# 6_3-axis-accelerometer.net
KiCad netlist of a schematic drawn in Altium Designer
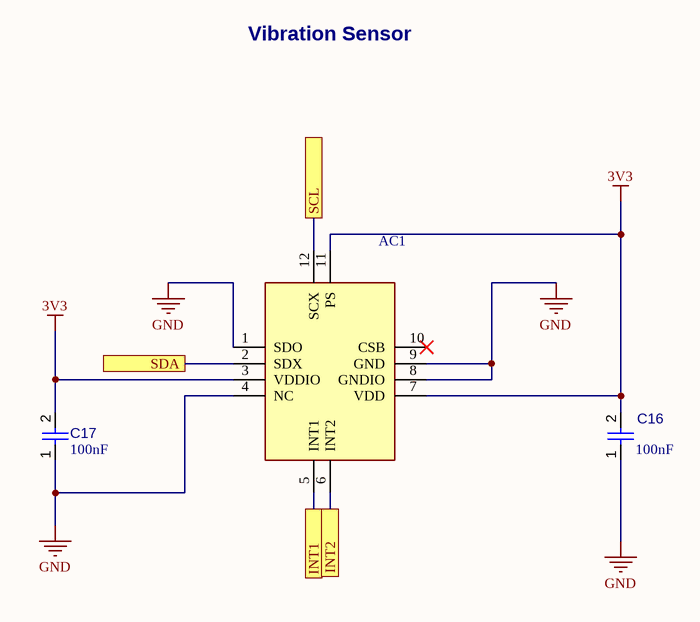
[diagram p0: [6]3-axis-accelerometer.SchDoc]

(export (version "E")
  (design (tool "Eeschema 10.0.6"))
  (components
    (comp (ref "AC1")
      (value "BMA490L")
      (footprint "BMA280")
      (description "BMA490L Accelerometer")
      (fields
        (field (name "MANUFACTURER_PART_NUMBER") "BMA280")
        (field (name "MOUSER PART NUMBER") "262-BMA280")
      )
      (libsource (lib "PCB_High_Voltage_Sensor") (part "BMA280"))
    )
    (comp (ref "C16")
      (value "100nF")
      (footprint "CAPC1608X90X40ML10T20")
      (description "Chip Capacitor, 100 nF, +/- 10%, 50 V, 0603 (1608 Metric)")
      (fields (field (name "TOLERANCE") "10%") (field (name "Comment") "Capacitor 100 nF +/-10% 50 V 0603"))
      (libsource (lib "Latium Technologies") (part "CAP-NP-2"))
    )
    (comp (ref "C17")
      (value "100nF")
      (footprint "CAPC1608X90X40ML10T20")
      (description "Chip Capacitor, 100 nF, +/- 10%, 50 V, 0603 (1608 Metric)")
      (fields (field (name "TOLERANCE") "10%") (field (name "Comment") "Capacitor 100 nF +/-10% 50 V 0603"))
      (libsource (lib "Latium Technologies") (part "CAP-NP-2"))
    )
  )
  (nets
    (net (code "1") (name "/INT1") (class "Default")
      (node (ref "AC1") (pin "5") (pinfunction "INT1_5") (pintype "passive"))
    )
    (net (code "2") (name "/INT2") (class "Default")
      (node (ref "AC1") (pin "6") (pinfunction "INT2_6") (pintype "passive"))
    )
    (net (code "3") (name "/SCL") (class "Default")
      (node (ref "AC1") (pin "12") (pinfunction "SCX_12") (pintype "passive"))
    )
    (net (code "4") (name "/SDA") (class "Default")
      (node (ref "AC1") (pin "2") (pinfunction "SDX_2") (pintype "passive"))
    )
    (net (code "5") (name "3V3") (class "Default")
      (node (ref "AC1") (pin "11") (pinfunction "PS_11") (pintype "passive"))
      (node (ref "AC1") (pin "3") (pinfunction "VDDIO_3") (pintype "passive"))
      (node (ref "AC1") (pin "7") (pinfunction "VDD_7") (pintype "passive"))
      (node (ref "C16") (pin "2") (pinfunction "2_2") (pintype "passive"))
      (node (ref "C17") (pin "2") (pinfunction "2_2") (pintype "passive"))
    )
    (net (code "6") (name "GND") (class "Default")
      (node (ref "AC1") (pin "1") (pinfunction "SDO_1") (pintype "passive"))
      (node (ref "AC1") (pin "4") (pinfunction "NC_4") (pintype "passive"))
      (node (ref "AC1") (pin "8") (pinfunction "GNDIO_8") (pintype "passive"))
      (node (ref "AC1") (pin "9") (pinfunction "GND_9") (pintype "passive"))
      (node (ref "C16") (pin "1") (pinfunction "1_1") (pintype "passive"))
      (node (ref "C17") (pin "1") (pinfunction "1_1") (pintype "passive"))
    )
    (net (code "7") (name "unconnected-(AC1-CSB-Pad10)") (class "Default")
      (node (ref "AC1") (pin "10") (pinfunction "CSB_10") (pintype "passive+no_connect"))
    )
  )
)
